# Bater_aRecargable.net
KiCad netlist of a schematic drawn in Altium Designer
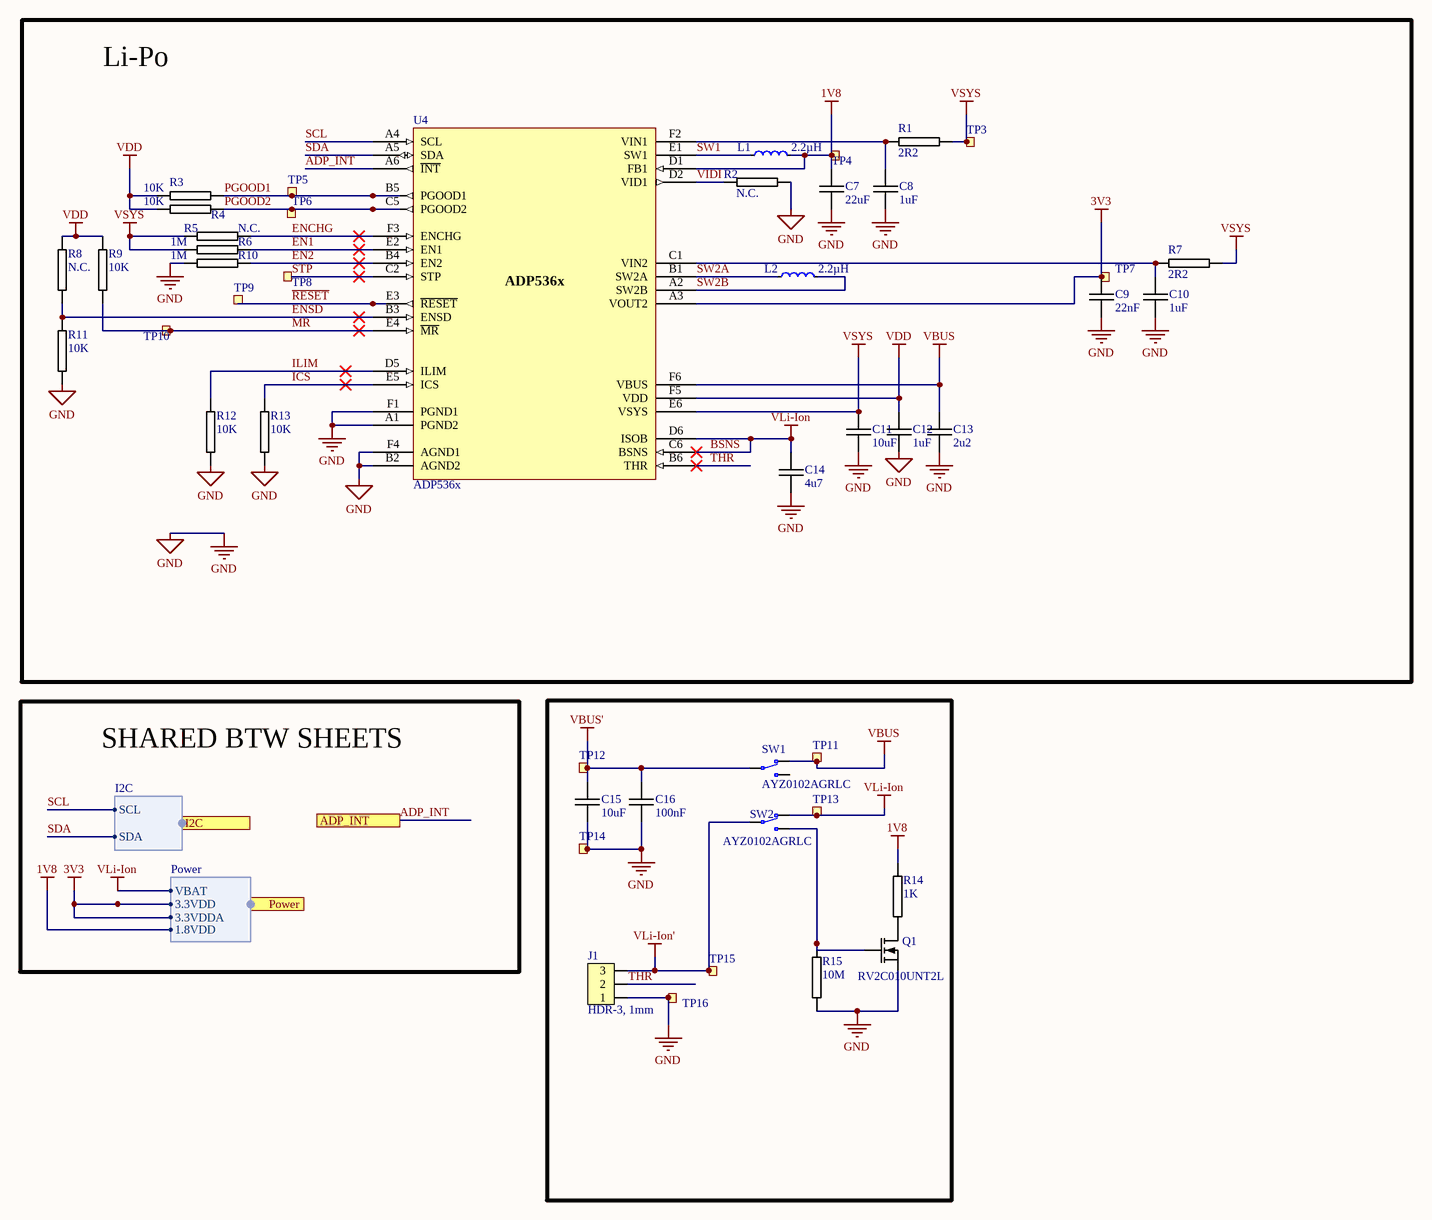
[diagram p0: BateríaRecargable.SchDoc]

(export (version "E")
  (design (tool "Eeschema 10.0.6"))
  (components
    (comp (ref "C7")
      (value "22uF")
      (footprint "0603C-GENERIC")
      (libsource (lib "vh_altium_library") (part "0603C-000"))
    )
    (comp (ref "C8")
      (value "1uF")
      (footprint "0402C-GENERIC")
      (description "CAPACITOR 0402 CERAMIC")
      (libsource (lib "vh_altium_library") (part "0402C-1UF-10V-X5R-SAM"))
    )
    (comp (ref "C9")
      (value "22nF")
      (footprint "0603C-GENERIC")
      (description "CAPACITOR 0603 CERAMIC")
      (libsource (lib "vh_altium_library") (part "0603C-22NF-50V-X7R-TDK"))
    )
    (comp (ref "C10")
      (value "1uF")
      (footprint "0603C-GENERIC")
      (description "CAPACITOR 0603 CERAMIC")
      (fields
        (field (name "MANUFACTURER") "TDK Corporation")
        (field (name "MANUFACTURER PART NUMBER") "C1608X5R1A105K")
      )
      (libsource (lib "vh_altium_library") (part "0603C-1UF-10V-X5R-TDK"))
    )
    (comp (ref "C11")
      (value "10uF")
      (footprint "0603C-GENERIC")
      (description "CAPACITOR 0603 CERAMIC")
      (fields
        (field (name "MANUFACTURER PART NUMBER") "C1608X5R0J106M")
        (field (name "MANUFACTURER") "TDK Corporation")
      )
      (libsource (lib "vh_altium_library") (part "0603C-10UF-10V-X5R-TDK"))
    )
    (comp (ref "C12")
      (value "1uF")
      (footprint "0603C-GENERIC")
      (description "CAPACITOR 0603 CERAMIC")
      (fields
        (field (name "MANUFACTURER") "TDK Corporation")
        (field (name "MANUFACTURER PART NUMBER") "C1608X5R1A105K")
      )
      (libsource (lib "vh_altium_library") (part "0603C-1UF-10V-X5R-TDK"))
    )
    (comp (ref "C13")
      (value "2u2")
      (footprint "0603C-2U2")
      (description "CAPACITOR 0603 CERAMIC")
      (fields
        (field (name "MANUFACTURER") "TDK Corporation")
        (field (name "MANUFACTURER PART NUMBER") "C1608X5R1A225K")
      )
      (libsource (lib "vh_altium_library") (part "0603C-2U2-10V-X5R-TDK"))
    )
    (comp (ref "C14")
      (value "4u7")
      (footprint "0603C-GENERIC")
      (description "CAPACITOR 0603 CERAMIC")
      (libsource (lib "vh_altium_library") (part "0603C-4U7-10V-X5R-SAM"))
    )
    (comp (ref "C15")
      (value "10uF")
      (footprint "0603C-GENERIC")
      (description "CAPACITOR 0603 CERAMIC")
      (fields
        (field (name "MANUFACTURER PART NUMBER") "C1608X5R0J106M")
        (field (name "MANUFACTURER") "TDK Corporation")
      )
      (libsource (lib "vh_altium_library") (part "0603C-10UF-10V-X5R-TDK"))
    )
    (comp (ref "C16")
      (value "100nF")
      (footprint "0603C-GENERIC")
      (description "CAPACITOR 0603 CERAMIC")
      (fields
        (field (name "MANUFACTURER PART NUMBER") "C1608X7R1E104K")
        (field (name "MANUFACTURER") "TDK Corporation")
      )
      (libsource (lib "vh_altium_library") (part "0603C-100NF-25V-X7R-TDK"))
    )
    (comp (ref "J1")
      (value "HDR-3, 1mm")
      (footprint "SM03B-SRSS-TB")
      (description "1.0mm pitch connector side entry SMD")
      (fields
        (field (name "PART NUMBER") "SM03B-SRSS-TB")
        (field (name "MANUFACTURER") "JST")
        (field (name "PUBLISHER") "Nordic Semiconductor")
      )
      (libsource (lib "FEEL2020") (part "SM03B-SRSS-TB"))
    )
    (comp (ref "L1")
      (value "2.2µH")
      (footprint "INDC2016X18N")
      (description "Shielded Multilayer Inductor, 1.2A, ±20%, 110mOhm, Q=10 @ 1MHz")
      (fields
        (field (name "PART NUMBER") "L0806-2µ2-1.2A-110mOhm")
        (field (name "MANUFACTURER") "Wurth Electronics")
        (field (name "PUBLISHER") "Nordic Semiconductor")
      )
      (libsource (lib "FEEL2020") (part "74479776222A"))
    )
    (comp (ref "L2")
      (value "2.2µH")
      (footprint "INDC2016X18N")
      (description "Shielded Multilayer Inductor, 1.2A, ±20%, 110mOhm, Q=10 @ 1MHz")
      (fields
        (field (name "PART NUMBER") "L0806-2µ2-1.2A-110mOhm")
        (field (name "MANUFACTURER") "Wurth Electronics")
        (field (name "PUBLISHER") "Nordic Semiconductor")
      )
      (libsource (lib "FEEL2020") (part "74479776222A"))
    )
    (comp (ref "Q1")
      (value "RV2C010UNT2L")
      (footprint "DFN65P100X40-3L")
      (description "N-Channel MOSFET, 20V, 1A, 470mOhm, 400mW")
      (fields
        (field (name "MANUFACTURER") "Rohm Semiconductor")
        (field (name "PUBLISHER") "Nordic Semiconductor")
      )
      (libsource (lib "FEEL2020") (part "RV2C010UNT2L"))
    )
    (comp (ref "R1")
      (value "2R2")
      (footprint "0603R-GENERIC")
      (description "2R2 Resistor")
      (libsource (lib "vh_altium_library") (part "0603R-000"))
    )
    (comp (ref "R2")
      (value "N.C.")
      (footprint "0603R-GENERIC")
      (libsource (lib "vh_altium_library") (part "0603R-000"))
    )
    (comp (ref "R3")
      (value "10K")
      (footprint "0603R-10K")
      (description "GENERIC RESISTOR 0603")
      (fields (field (name "MANUFACTURER") "Stackpole Electronics Inc") (field (name "TOLERANCE") "±1%"))
      (libsource (lib "vh_altium_library") (part "0603R-10K"))
    )
    (comp (ref "R4")
      (value "10K")
      (footprint "0603R-10K")
      (description "GENERIC RESISTOR 0603")
      (fields (field (name "MANUFACTURER") "Stackpole Electronics Inc") (field (name "TOLERANCE") "±1%"))
      (libsource (lib "vh_altium_library") (part "0603R-10K"))
    )
    (comp (ref "R5")
      (value "N.C.")
      (footprint "0603R-GENERIC")
      (libsource (lib "vh_altium_library") (part "0603R-000"))
    )
    (comp (ref "R6")
      (value "1M")
      (footprint "0603R-GENERIC")
      (description "GENERIC RESISTOR 0603")
      (fields
        (field (name "MANUFACTURER") "Stackpole Electronics Inc")
        (field (name "MANUFACTURER PART NUMBER") "RMCF 1/16 1M 1% R")
      )
      (libsource (lib "vh_altium_library") (part "0603R-1M"))
    )
    (comp (ref "R7")
      (value "2R2")
      (footprint "0603R-GENERIC")
      (description "2R2 Resistor")
      (libsource (lib "vh_altium_library") (part "0603R-000"))
    )
    (comp (ref "R8")
      (value "N.C.")
      (footprint "0603R-GENERIC")
      (libsource (lib "vh_altium_library") (part "0603R-000"))
    )
    (comp (ref "R9")
      (value "10K")
      (footprint "0603R-10K")
      (description "GENERIC RESISTOR 0603")
      (fields (field (name "MANUFACTURER") "Stackpole Electronics Inc") (field (name "TOLERANCE") "±1%"))
      (libsource (lib "vh_altium_library") (part "0603R-10K"))
    )
    (comp (ref "R10")
      (value "1M")
      (footprint "0603R-GENERIC")
      (description "GENERIC RESISTOR 0603")
      (fields
        (field (name "MANUFACTURER") "Stackpole Electronics Inc")
        (field (name "MANUFACTURER PART NUMBER") "RMCF 1/16 1M 1% R")
      )
      (libsource (lib "vh_altium_library") (part "0603R-1M"))
    )
    (comp (ref "R11")
      (value "10K")
      (footprint "0603R-10K")
      (description "GENERIC RESISTOR 0603")
      (fields (field (name "MANUFACTURER") "Stackpole Electronics Inc") (field (name "TOLERANCE") "±1%"))
      (libsource (lib "vh_altium_library") (part "0603R-10K"))
    )
    (comp (ref "R12")
      (value "10K")
      (footprint "0603R-10K")
      (description "GENERIC RESISTOR 0603")
      (fields (field (name "MANUFACTURER") "Stackpole Electronics Inc") (field (name "TOLERANCE") "±1%"))
      (libsource (lib "vh_altium_library") (part "0603R-10K"))
    )
    (comp (ref "R13")
      (value "10K")
      (footprint "0603R-10K")
      (description "GENERIC RESISTOR 0603")
      (fields (field (name "MANUFACTURER") "Stackpole Electronics Inc") (field (name "TOLERANCE") "±1%"))
      (libsource (lib "vh_altium_library") (part "0603R-10K"))
    )
    (comp (ref "R14")
      (value "1K")
      (footprint "0603R-1k")
      (description "GENERIC RESISTOR 0603")
      (fields
        (field (name "MANUFACTURER PART NUMBER") "RMCF 1/16 1K 1% R")
        (field (name "MANUFACTURER") "Stackpole Electronics Inc")
      )
      (libsource (lib "vh_altium_library") (part "0603R-1K"))
    )
    (comp (ref "R15")
      (value "10M")
      (footprint "0603R-GENERIC")
      (description "GENERIC RESISTOR 0603")
      (fields (field (name "TOLERANCE") "±5%") (field (name "MANUFACTURER PART NUMBER") "RMCF 1/16 10M 5% R"))
      (libsource (lib "vh_altium_library") (part "0603R-10M"))
    )
    (comp (ref "SW1")
      (value "AYZ0102AGRLC")
      (footprint "AYZ0102AGRLC")
      (description "Miniature slide switch, SPDT, Right-Angle, ON-ON, 12V, 100mA")
      (fields (field (name "MANUFACTURER") "C&K") (field (name "PUBLISHER") "Nordic Semiconductor"))
      (libsource (lib "FEEL2020") (part "AYZ0102AGRLC"))
    )
    (comp (ref "SW2")
      (value "AYZ0102AGRLC")
      (footprint "AYZ0102AGRLC")
      (description "Miniature slide switch, SPDT, Right-Angle, ON-ON, 12V, 100mA")
      (fields (field (name "MANUFACTURER") "C&K") (field (name "PUBLISHER") "Nordic Semiconductor"))
      (libsource (lib "FEEL2020") (part "AYZ0102AGRLC"))
    )
    (comp (ref "TP3")
      (value "Ø1.0mm,SMD")
      (footprint "TP_SMD_Ø1.0mm")
      (description "1.0mm circular SMD testpad")
      (fields
        (field (name "PART NUMBER") "TP_SMD_Ø1.0MM")
        (field (name "MANUFACTURER") "Nordic Semiconductor")
        (field (name "PUBLISHER") "Nordic Semiconductor")
      )
      (libsource (lib "") (part "TP_SMD_Ø1.0MM_3"))
    )
    (comp (ref "TP4")
      (value "Ø1.0mm,SMD")
      (footprint "TP_SMD_Ø1.0mm")
      (description "1.0mm circular SMD testpad")
      (fields
        (field (name "PART NUMBER") "TP_SMD_Ø1.0MM")
        (field (name "MANUFACTURER") "Nordic Semiconductor")
        (field (name "PUBLISHER") "Nordic Semiconductor")
      )
      (libsource (lib "") (part "TP_SMD_Ø1.0MM_3"))
    )
    (comp (ref "TP5")
      (value "Ø1.0mm,SMD")
      (footprint "TP_SMD_Ø1.0mm")
      (description "1.0mm circular SMD testpad")
      (fields
        (field (name "PART NUMBER") "TP_SMD_Ø1.0MM")
        (field (name "MANUFACTURER") "Nordic Semiconductor")
        (field (name "PUBLISHER") "Nordic Semiconductor")
      )
      (libsource (lib "") (part "TP_SMD_Ø1.0MM_1"))
    )
    (comp (ref "TP6")
      (value "Ø1.0mm,SMD")
      (footprint "TP_SMD_Ø1.0mm")
      (description "1.0mm circular SMD testpad")
      (fields
        (field (name "PART NUMBER") "TP_SMD_Ø1.0MM")
        (field (name "MANUFACTURER") "Nordic Semiconductor")
        (field (name "PUBLISHER") "Nordic Semiconductor")
      )
      (libsource (lib "FEEL2020") (part "TP_SMD_Ø1.0MM"))
    )
    (comp (ref "TP7")
      (value "Ø1.0mm,SMD")
      (footprint "TP_SMD_Ø1.0mm")
      (description "1.0mm circular SMD testpad")
      (fields
        (field (name "PART NUMBER") "TP_SMD_Ø1.0MM")
        (field (name "MANUFACTURER") "Nordic Semiconductor")
        (field (name "PUBLISHER") "Nordic Semiconductor")
      )
      (libsource (lib "") (part "TP_SMD_Ø1.0MM_3"))
    )
    (comp (ref "TP8")
      (value "Ø1.0mm,SMD")
      (footprint "TP_SMD_Ø1.0mm")
      (description "1.0mm circular SMD testpad")
      (fields
        (field (name "PART NUMBER") "TP_SMD_Ø1.0MM")
        (field (name "MANUFACTURER") "Nordic Semiconductor")
        (field (name "PUBLISHER") "Nordic Semiconductor")
      )
      (libsource (lib "") (part "TP_SMD_Ø1.0MM_2"))
    )
    (comp (ref "TP9")
      (value "Ø1.0mm,SMD")
      (footprint "TP_SMD_Ø1.0mm")
      (description "1.0mm circular SMD testpad")
      (fields
        (field (name "PART NUMBER") "TP_SMD_Ø1.0MM")
        (field (name "MANUFACTURER") "Nordic Semiconductor")
        (field (name "PUBLISHER") "Nordic Semiconductor")
      )
      (libsource (lib "") (part "TP_SMD_Ø1.0MM_1"))
    )
    (comp (ref "TP10")
      (value "Ø1.0mm,SMD")
      (footprint "TP_SMD_Ø1.0mm")
      (description "1.0mm circular SMD testpad")
      (fields
        (field (name "PART NUMBER") "TP_SMD_Ø1.0MM")
        (field (name "MANUFACTURER") "Nordic Semiconductor")
        (field (name "PUBLISHER") "Nordic Semiconductor")
      )
      (libsource (lib "") (part "TP_SMD_Ø1.0MM_2"))
    )
    (comp (ref "TP11")
      (value "Ø1.0mm,SMD")
      (footprint "TP_SMD_Ø1.0mm")
      (description "1.0mm circular SMD testpad")
      (fields
        (field (name "PART NUMBER") "TP_SMD_Ø1.0MM")
        (field (name "MANUFACTURER") "Nordic Semiconductor")
        (field (name "PUBLISHER") "Nordic Semiconductor")
      )
      (libsource (lib "") (part "TP_SMD_Ø1.0MM_1"))
    )
    (comp (ref "TP12")
      (value "Ø1.0mm,SMD")
      (footprint "TP_SMD_Ø1.0mm")
      (description "1.0mm circular SMD testpad")
      (fields
        (field (name "PART NUMBER") "TP_SMD_Ø1.0MM")
        (field (name "MANUFACTURER") "Nordic Semiconductor")
        (field (name "PUBLISHER") "Nordic Semiconductor")
      )
      (libsource (lib "") (part "TP_SMD_Ø1.0MM_2"))
    )
    (comp (ref "TP13")
      (value "Ø1.0mm,SMD")
      (footprint "TP_SMD_Ø1.0mm")
      (description "1.0mm circular SMD testpad")
      (fields
        (field (name "PART NUMBER") "TP_SMD_Ø1.0MM")
        (field (name "MANUFACTURER") "Nordic Semiconductor")
        (field (name "PUBLISHER") "Nordic Semiconductor")
      )
      (libsource (lib "") (part "TP_SMD_Ø1.0MM_1"))
    )
    (comp (ref "TP14")
      (value "Ø1.0mm,SMD")
      (footprint "TP_SMD_Ø1.0mm")
      (description "1.0mm circular SMD testpad")
      (fields
        (field (name "PART NUMBER") "TP_SMD_Ø1.0MM")
        (field (name "MANUFACTURER") "Nordic Semiconductor")
        (field (name "PUBLISHER") "Nordic Semiconductor")
      )
      (libsource (lib "") (part "TP_SMD_Ø1.0MM_2"))
    )
    (comp (ref "TP15")
      (value "Ø1.0mm,SMD")
      (footprint "TP_SMD_Ø1.0mm")
      (description "1.0mm circular SMD testpad")
      (fields
        (field (name "PART NUMBER") "TP_SMD_Ø1.0MM")
        (field (name "MANUFACTURER") "Nordic Semiconductor")
        (field (name "PUBLISHER") "Nordic Semiconductor")
      )
      (libsource (lib "") (part "TP_SMD_Ø1.0MM_3"))
    )
    (comp (ref "TP16")
      (value "Ø1.0mm,SMD")
      (footprint "TP_SMD_Ø1.0mm")
      (description "1.0mm circular SMD testpad")
      (fields
        (field (name "PART NUMBER") "TP_SMD_Ø1.0MM")
        (field (name "MANUFACTURER") "Nordic Semiconductor")
        (field (name "PUBLISHER") "Nordic Semiconductor")
      )
      (libsource (lib "") (part "TP_SMD_Ø1.0MM_3"))
    )
    (comp (ref "U4")
      (value "ADP536x")
      (footprint "BGA32C40P6X6_238X238X56")
      (description "Advanced Battery Management PMIC With Ultralow Iq Buck and Buck-Boost")
      (fields
        (field (name "MANUFACTURER") "Analog Devices")
        (field (name "PUBLISHER") "Nordic Semiconductor")
      )
      (libsource (lib "FEEL2020") (part "ADP536x"))
    )
  )
  (nets
    (net (code "3") (name "/ADP_INT") (class "Default")
      (node (ref "U4") (pin "A6") (pinfunction "~{INT}_A6") (pintype "output"))
    )
    (net (code "4") (name "/EN1") (class "Default")
      (node (ref "R6") (pin "2") (pintype "passive"))
      (node (ref "U4") (pin "E2") (pinfunction "EN1_E2") (pintype "input"))
    )
    (net (code "5") (name "/EN2") (class "Default")
      (node (ref "R10") (pin "2") (pintype "passive"))
      (node (ref "U4") (pin "B4") (pinfunction "EN2_B4") (pintype "input"))
    )
    (net (code "6") (name "/ENCHG") (class "Default")
      (node (ref "R5") (pin "2") (pintype "passive"))
      (node (ref "U4") (pin "F3") (pinfunction "ENCHG_F3") (pintype "input"))
    )
    (net (code "7") (name "/ENSD") (class "Default")
      (node (ref "R11") (pin "1") (pintype "passive"))
      (node (ref "R8") (pin "2") (pintype "passive"))
      (node (ref "U4") (pin "B3") (pinfunction "ENSD_B3") (pintype "input"))
    )
    (net (code "8") (name "/ICS") (class "Default")
      (node (ref "R13") (pin "1") (pintype "passive"))
      (node (ref "U4") (pin "E5") (pinfunction "ICS_E5") (pintype "input"))
    )
    (net (code "9") (name "/ILIM") (class "Default")
      (node (ref "R12") (pin "1") (pintype "passive"))
      (node (ref "U4") (pin "D5") (pinfunction "ILIM_D5") (pintype "input"))
    )
    (net (code "10") (name "/MR") (class "Default")
      (node (ref "R9") (pin "2") (pintype "passive"))
      (node (ref "TP10") (pin "1") (pinfunction "1_1") (pintype "passive"))
      (node (ref "U4") (pin "E4") (pinfunction "~{MR}_E4") (pintype "input"))
    )
    (net (code "11") (name "/PGOOD1") (class "Default")
      (node (ref "R3") (pin "2") (pintype "passive"))
      (node (ref "TP5") (pin "1") (pinfunction "1_1") (pintype "passive"))
      (node (ref "U4") (pin "B5") (pinfunction "PGOOD1_B5") (pintype "output"))
    )
    (net (code "12") (name "/PGOOD2") (class "Default")
      (node (ref "R4") (pin "2") (pintype "passive"))
      (node (ref "TP6") (pin "1") (pinfunction "1_1") (pintype "passive"))
      (node (ref "U4") (pin "C5") (pinfunction "PGOOD2_C5") (pintype "output"))
    )
    (net (code "13") (name "/SCL") (class "Default")
      (node (ref "U4") (pin "A4") (pinfunction "SCL_A4") (pintype "input"))
    )
    (net (code "14") (name "/SDA") (class "Default")
      (node (ref "U4") (pin "A5") (pinfunction "SDA_A5") (pintype "bidirectional"))
    )
    (net (code "15") (name "/STP") (class "Default")
      (node (ref "TP8") (pin "1") (pinfunction "1_1") (pintype "passive"))
      (node (ref "U4") (pin "C2") (pinfunction "STP_C2") (pintype "input"))
    )
    (net (code "16") (name "/SW1") (class "Default")
      (node (ref "L1") (pin "1") (pinfunction "1_1") (pintype "passive"))
      (node (ref "U4") (pin "E1") (pinfunction "SW1_E1") (pintype "power_in"))
    )
    (net (code "17") (name "/SW2A") (class "Default")
      (node (ref "L2") (pin "1") (pinfunction "1_1") (pintype "passive"))
      (node (ref "U4") (pin "B1") (pinfunction "SW2A_B1") (pintype "power_in"))
    )
    (net (code "18") (name "/SW2B") (class "Default")
      (node (ref "L2") (pin "2") (pinfunction "2_2") (pintype "passive"))
      (node (ref "U4") (pin "A2") (pinfunction "SW2B_A2") (pintype "power_in"))
    )
    (net (code "19") (name "/THR") (class "Default")
      (node (ref "J1") (pin "2") (pinfunction "2_2") (pintype "passive"))
      (node (ref "U4") (pin "B6") (pinfunction "THR_B6") (pintype "input"))
    )
    (net (code "20") (name "/VIDI") (class "Default")
      (node (ref "R2") (pin "1") (pintype "passive"))
      (node (ref "U4") (pin "D2") (pinfunction "VID1_D2") (pintype "output"))
    )
    (net (code "23") (name "/~{RESET}") (class "Default")
      (node (ref "TP9") (pin "1") (pinfunction "1_1") (pintype "passive"))
      (node (ref "U4") (pin "E3") (pinfunction "~{RESET}_E3") (pintype "output"))
    )
    (net (code "24") (name "1V8") (class "Default")
      (node (ref "C7") (pin "1") (pintype "passive"))
      (node (ref "L1") (pin "2") (pinfunction "2_2") (pintype "passive"))
      (node (ref "R14") (pin "1") (pintype "passive"))
      (node (ref "TP4") (pin "1") (pinfunction "1_1") (pintype "passive"))
      (node (ref "U4") (pin "D1") (pinfunction "FB1_D1") (pintype "input"))
    )
    (net (code "25") (name "3V3") (class "Default")
      (node (ref "C9") (pin "1") (pintype "passive"))
      (node (ref "TP7") (pin "1") (pinfunction "1_1") (pintype "passive"))
      (node (ref "U4") (pin "A3") (pinfunction "VOUT2_A3") (pintype "power_in"))
    )
    (net (code "26") (name "GND") (class "Default")
      (node (ref "C10") (pin "2") (pintype "passive"))
      (node (ref "C11") (pin "2") (pintype "passive"))
      (node (ref "C12") (pin "2") (pintype "passive"))
      (node (ref "C13") (pin "2") (pintype "passive"))
      (node (ref "C14") (pin "2") (pintype "passive"))
      (node (ref "C15") (pin "2") (pintype "passive"))
      (node (ref "C16") (pin "2") (pintype "passive"))
      (node (ref "C7") (pin "2") (pintype "passive"))
      (node (ref "C8") (pin "2") (pintype "passive"))
      (node (ref "C9") (pin "2") (pintype "passive"))
      (node (ref "J1") (pin "1") (pinfunction "1_1") (pintype "passive"))
      (node (ref "Q1") (pin "2") (pinfunction "S_2") (pintype "passive"))
      (node (ref "R10") (pin "1") (pintype "passive"))
      (node (ref "R11") (pin "2") (pintype "passive"))
      (node (ref "R12") (pin "2") (pintype "passive"))
      (node (ref "R13") (pin "2") (pintype "passive"))
      (node (ref "R15") (pin "2") (pintype "passive"))
      (node (ref "R2") (pin "2") (pintype "passive"))
      (node (ref "TP14") (pin "1") (pinfunction "1_1") (pintype "passive"))
      (node (ref "TP16") (pin "1") (pinfunction "1_1") (pintype "passive"))
      (node (ref "U4") (pin "A1") (pinfunction "PGND2_A1") (pintype "power_in"))
      (node (ref "U4") (pin "B2") (pinfunction "AGND2_B2") (pintype "power_in"))
      (node (ref "U4") (pin "F1") (pinfunction "PGND1_F1") (pintype "power_in"))
      (node (ref "U4") (pin "F4") (pinfunction "AGND1_F4") (pintype "power_in"))
    )
    (net (code "27") (name "Net-(Q1-D)") (class "Default")
      (node (ref "Q1") (pin "3") (pinfunction "D_3") (pintype "passive"))
      (node (ref "R14") (pin "2") (pintype "passive"))
    )
    (net (code "28") (name "Net-(Q1-G)") (class "Default")
      (node (ref "Q1") (pin "1") (pinfunction "G_1") (pintype "passive"))
      (node (ref "R15") (pin "1") (pintype "passive"))
      (node (ref "SW2") (pin "3") (pinfunction "N.O_3") (pintype "passive"))
    )
    (net (code "29") (name "Net-(U4-VIN1)") (class "Default")
      (node (ref "C8") (pin "1") (pintype "passive"))
      (node (ref "R1") (pin "1") (pintype "passive"))
      (node (ref "U4") (pin "F2") (pinfunction "VIN1_F2") (pintype "power_in"))
    )
    (net (code "30") (name "Net-(U4-VIN2)") (class "Default")
      (node (ref "C10") (pin "1") (pintype "passive"))
      (node (ref "R7") (pin "1") (pintype "passive"))
      (node (ref "U4") (pin "C1") (pinfunction "VIN2_C1") (pintype "power_in"))
    )
    (net (code "31") (name "VBUS") (class "Default")
      (node (ref "C13") (pin "1") (pintype "passive"))
      (node (ref "SW1") (pin "1") (pinfunction "N.C_1") (pintype "passive"))
      (node (ref "TP11") (pin "1") (pinfunction "1_1") (pintype "passive"))
      (node (ref "U4") (pin "F6") (pinfunction "VBUS_F6") (pintype "power_in"))
    )
    (net (code "32") (name "VBUS'") (class "Default")
      (node (ref "C15") (pin "1") (pintype "passive"))
      (node (ref "C16") (pin "1") (pintype "passive"))
      (node (ref "SW1") (pin "2") (pinfunction "COM_2") (pintype "passive"))
      (node (ref "TP12") (pin "1") (pinfunction "1_1") (pintype "passive"))
    )
    (net (code "33") (name "VDD") (class "Default")
      (node (ref "C12") (pin "1") (pintype "passive"))
      (node (ref "R3") (pin "1") (pintype "passive"))
      (node (ref "R4") (pin "1") (pintype "passive"))
      (node (ref "R8") (pin "1") (pintype "passive"))
      (node (ref "R9") (pin "1") (pintype "passive"))
      (node (ref "U4") (pin "F5") (pinfunction "VDD_F5") (pintype "power_in"))
    )
    (net (code "34") (name "VLi-Ion") (class "Default")
      (node (ref "C14") (pin "1") (pintype "passive"))
      (node (ref "SW2") (pin "1") (pinfunction "N.C_1") (pintype "passive"))
      (node (ref "TP13") (pin "1") (pinfunction "1_1") (pintype "passive"))
      (node (ref "U4") (pin "C6") (pinfunction "BSNS_C6") (pintype "input"))
      (node (ref "U4") (pin "D6") (pinfunction "ISOB_D6") (pintype "power_in"))
    )
    (net (code "35") (name "VLi-Ion'") (class "Default")
      (node (ref "J1") (pin "3") (pinfunction "3_3") (pintype "passive"))
      (node (ref "SW2") (pin "2") (pinfunction "COM_2") (pintype "passive"))
      (node (ref "TP15") (pin "1") (pinfunction "1_1") (pintype "passive"))
    )
    (net (code "36") (name "VSYS") (class "Default")
      (node (ref "C11") (pin "1") (pintype "passive"))
      (node (ref "R1") (pin "2") (pintype "passive"))
      (node (ref "R5") (pin "1") (pintype "passive"))
      (node (ref "R6") (pin "1") (pintype "passive"))
      (node (ref "R7") (pin "2") (pintype "passive"))
      (node (ref "TP3") (pin "1") (pinfunction "1_1") (pintype "passive"))
      (node (ref "U4") (pin "E6") (pinfunction "VSYS_E6") (pintype "power_in"))
    )
    (net (code "37") (name "unconnected-(SW1-N.O-Pad3)") (class "Default")
      (node (ref "SW1") (pin "3") (pinfunction "N.O_3") (pintype "passive"))
    )
  )
)
